# Connector.net
KiCad netlist of a schematic drawn in Altium Designer
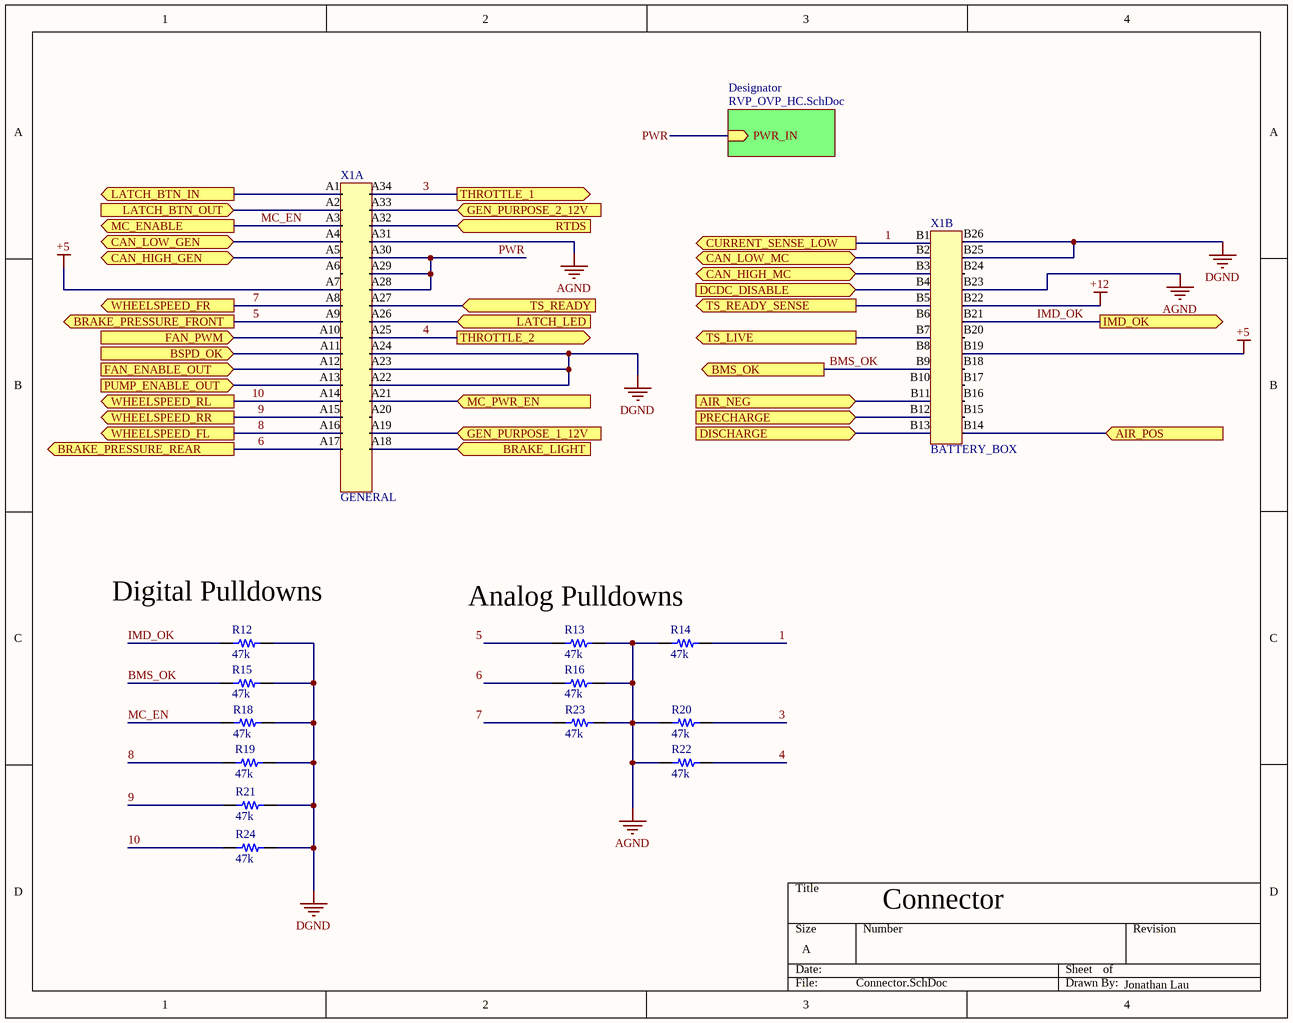
[diagram p0: Connector.SchDoc]

(export (version "E")
  (design (tool "Eeschema 10.0.6"))
  (components
    (comp (ref "R12")
      (value "47k")
      (footprint "RES 0805/2012")
      (fields
        (field (name "TOLERANCE") "1%")
        (field (name "POWER") "1/10W")
        (field (name "Comment") "Resistor 47k 0805 1/10W 1%")
        (field (name "CREATED_BY") "Nick Mah")
      )
      (libsource (lib "Altium-Lib") (part "Resistor"))
    )
    (comp (ref "R13")
      (value "47k")
      (footprint "RES 0805/2012")
      (fields
        (field (name "TOLERANCE") "5%")
        (field (name "POWER") "1/10W")
        (field (name "Comment") "Resistor 47k 0805 1/10W 5%")
        (field (name "CREATED_BY") "Nick Mah")
      )
      (libsource (lib "Altium-Lib") (part "Resistor"))
    )
    (comp (ref "R14")
      (value "47k")
      (footprint "RES 0805/2012")
      (fields
        (field (name "TOLERANCE") "5%")
        (field (name "POWER") "1/10W")
        (field (name "Comment") "Resistor 47k 0805 1/10W 5%")
        (field (name "CREATED_BY") "Nick Mah")
      )
      (libsource (lib "Altium-Lib") (part "Resistor"))
    )
    (comp (ref "R15")
      (value "47k")
      (footprint "RES 0805/2012")
      (fields
        (field (name "TOLERANCE") "1%")
        (field (name "POWER") "1/10W")
        (field (name "Comment") "Resistor 47k 0805 1/10W 1%")
        (field (name "CREATED_BY") "Nick Mah")
      )
      (libsource (lib "Altium-Lib") (part "Resistor"))
    )
    (comp (ref "R16")
      (value "47k")
      (footprint "RES 0805/2012")
      (fields
        (field (name "TOLERANCE") "5%")
        (field (name "POWER") "1/10W")
        (field (name "Comment") "Resistor 47k 0805 1/10W 5%")
        (field (name "CREATED_BY") "Nick Mah")
      )
      (libsource (lib "Altium-Lib") (part "Resistor"))
    )
    (comp (ref "R18")
      (value "47k")
      (footprint "RES 0805/2012")
      (fields
        (field (name "TOLERANCE") "1%")
        (field (name "POWER") "1/10W")
        (field (name "Comment") "Resistor 47k 0805 1/10W 1%")
        (field (name "CREATED_BY") "Nick Mah")
      )
      (libsource (lib "Altium-Lib") (part "Resistor"))
    )
    (comp (ref "R19")
      (value "47k")
      (footprint "RES 0805/2012")
      (fields
        (field (name "TOLERANCE") "5%")
        (field (name "POWER") "1/10W")
        (field (name "Comment") "Resistor 47k 0805 1/10W 5%")
        (field (name "CREATED_BY") "Nick Mah")
      )
      (libsource (lib "Altium-Lib") (part "Resistor"))
    )
    (comp (ref "R20")
      (value "47k")
      (footprint "RES 0805/2012")
      (fields
        (field (name "TOLERANCE") "5%")
        (field (name "POWER") "1/10W")
        (field (name "Comment") "Resistor 47k 0805 1/10W 5%")
        (field (name "CREATED_BY") "Nick Mah")
      )
      (libsource (lib "Altium-Lib") (part "Resistor"))
    )
    (comp (ref "R21")
      (value "47k")
      (footprint "RES 0805/2012")
      (fields
        (field (name "TOLERANCE") "5%")
        (field (name "POWER") "1/10W")
        (field (name "Comment") "Resistor 47k 0805 1/10W 5%")
        (field (name "CREATED_BY") "Nick Mah")
      )
      (libsource (lib "Altium-Lib") (part "Resistor"))
    )
    (comp (ref "R22")
      (value "47k")
      (footprint "RES 0805/2012")
      (fields
        (field (name "TOLERANCE") "5%")
        (field (name "POWER") "1/10W")
        (field (name "Comment") "Resistor 47k 0805 1/10W 5%")
        (field (name "CREATED_BY") "Nick Mah")
      )
      (libsource (lib "Altium-Lib") (part "Resistor"))
    )
    (comp (ref "R23")
      (value "47k")
      (footprint "RES 0805/2012")
      (fields
        (field (name "TOLERANCE") "5%")
        (field (name "POWER") "1/10W")
        (field (name "Comment") "Resistor 47k 0805 1/10W 5%")
        (field (name "CREATED_BY") "Nick Mah")
      )
      (libsource (lib "Altium-Lib") (part "Resistor"))
    )
    (comp (ref "R24")
      (value "47k")
      (footprint "RES 0805/2012")
      (fields
        (field (name "TOLERANCE") "5%")
        (field (name "POWER") "1/10W")
        (field (name "Comment") "Resistor 47k 0805 1/10W 5%")
        (field (name "CREATED_BY") "Nick Mah")
      )
      (libsource (lib "Altium-Lib") (part "Resistor"))
    )
    (comp (ref "X1")
      (value "GENERAL")
      (footprint "SUPERSEAL 60POS 90Deg")
      (description "90 Degree")
      (fields (field (name "MFRPARTNO") "3-6437285-2"))
      (libsource (lib "Altium-Lib") (part "CONN Superseal 60POS"))
    )
  )
  (nets
    (net (code "1") (name "+5") (class "Default")
      (node (ref "X1") (pin "A7") (pintype "bidirectional"))
      (node (ref "X1") (pin "B19") (pintype "bidirectional"))
    )
    (net (code "2") (name "+12") (class "Default") (node (ref "X1") (pin "B22") (pintype "bidirectional")))
    (net (code "3") (name "/1") (class "Default")
      (node (ref "R14") (pin "2") (pinfunction "2_2") (pintype "passive"))
      (node (ref "X1") (pin "B1") (pintype "bidirectional"))
    )
    (net (code "4") (name "/3") (class "Default")
      (node (ref "R20") (pin "2") (pinfunction "2_2") (pintype "passive"))
      (node (ref "X1") (pin "A34") (pintype "bidirectional"))
    )
    (net (code "5") (name "/4") (class "Default")
      (node (ref "R22") (pin "2") (pinfunction "2_2") (pintype "passive"))
      (node (ref "X1") (pin "A25") (pintype "bidirectional"))
    )
    (net (code "6") (name "/5") (class "Default")
      (node (ref "R13") (pin "1") (pinfunction "1_1") (pintype "passive"))
      (node (ref "X1") (pin "A9") (pintype "bidirectional"))
    )
    (net (code "7") (name "/6") (class "Default")
      (node (ref "R16") (pin "1") (pinfunction "1_1") (pintype "passive"))
      (node (ref "X1") (pin "A17") (pintype "bidirectional"))
    )
    (net (code "8") (name "/7") (class "Default")
      (node (ref "R23") (pin "1") (pinfunction "1_1") (pintype "passive"))
      (node (ref "X1") (pin "A8") (pintype "bidirectional"))
    )
    (net (code "9") (name "/8") (class "Default")
      (node (ref "R19") (pin "1") (pinfunction "1_1") (pintype "passive"))
      (node (ref "X1") (pin "A16") (pintype "bidirectional"))
    )
    (net (code "10") (name "/9") (class "Default")
      (node (ref "R21") (pin "1") (pinfunction "1_1") (pintype "passive"))
      (node (ref "X1") (pin "A15") (pintype "bidirectional"))
    )
    (net (code "11") (name "/10") (class "Default")
      (node (ref "R24") (pin "1") (pinfunction "1_1") (pintype "passive"))
      (node (ref "X1") (pin "A14") (pintype "bidirectional"))
    )
    (net (code "12") (name "/AIR_NEG") (class "Default")
      (node (ref "X1") (pin "B11") (pintype "bidirectional"))
    )
    (net (code "13") (name "/AIR_POS") (class "Default")
      (node (ref "X1") (pin "B14") (pintype "bidirectional"))
    )
    (net (code "14") (name "/BMS_OK") (class "Default")
      (node (ref "R15") (pin "1") (pinfunction "1_1") (pintype "passive"))
      (node (ref "X1") (pin "B9") (pintype "bidirectional"))
    )
    (net (code "15") (name "/BRAKE_LIGHT") (class "Default")
      (node (ref "X1") (pin "A18") (pintype "bidirectional"))
    )
    (net (code "16") (name "/BSPD_OK") (class "Default")
      (node (ref "X1") (pin "A11") (pintype "bidirectional"))
    )
    (net (code "17") (name "/CAN_HIGH_GEN") (class "Default")
      (node (ref "X1") (pin "A5") (pintype "bidirectional"))
    )
    (net (code "18") (name "/CAN_HIGH_MC") (class "Default")
      (node (ref "X1") (pin "B3") (pintype "bidirectional"))
    )
    (net (code "19") (name "/CAN_LOW_GEN") (class "Default")
      (node (ref "X1") (pin "A4") (pintype "bidirectional"))
    )
    (net (code "20") (name "/CAN_LOW_MC") (class "Default")
      (node (ref "X1") (pin "B2") (pintype "bidirectional"))
    )
    (net (code "21") (name "/DCDC_DISABLE") (class "Default")
      (node (ref "X1") (pin "B4") (pintype "bidirectional"))
    )
    (net (code "22") (name "/DISCHARGE") (class "Default")
      (node (ref "X1") (pin "B13") (pintype "bidirectional"))
    )
    (net (code "23") (name "/FAN_ENABLE_OUT") (class "Default")
      (node (ref "X1") (pin "A12") (pintype "bidirectional"))
    )
    (net (code "24") (name "/FAN_PWM") (class "Default")
      (node (ref "X1") (pin "A10") (pintype "bidirectional"))
    )
    (net (code "25") (name "/GEN_PURPOSE_1_12V") (class "Default")
      (node (ref "X1") (pin "A19") (pintype "bidirectional"))
    )
    (net (code "26") (name "/GEN_PURPOSE_2_12V") (class "Default")
      (node (ref "X1") (pin "A33") (pintype "bidirectional"))
    )
    (net (code "27") (name "/IMD_OK") (class "Default")
      (node (ref "R12") (pin "1") (pinfunction "1_1") (pintype "passive"))
      (node (ref "X1") (pin "B21") (pintype "bidirectional"))
    )
    (net (code "28") (name "/LATCH_BTN_IN") (class "Default")
      (node (ref "X1") (pin "A1") (pintype "bidirectional"))
    )
    (net (code "29") (name "/LATCH_BTN_OUT") (class "Default")
      (node (ref "X1") (pin "A2") (pintype "bidirectional"))
    )
    (net (code "30") (name "/LATCH_LED") (class "Default")
      (node (ref "X1") (pin "A26") (pintype "bidirectional"))
    )
    (net (code "31") (name "/MC_EN") (class "Default")
      (node (ref "R18") (pin "1") (pinfunction "1_1") (pintype "passive"))
      (node (ref "X1") (pin "A3") (pintype "bidirectional"))
    )
    (net (code "32") (name "/MC_PWR_EN") (class "Default")
      (node (ref "X1") (pin "A21") (pintype "bidirectional"))
    )
    (net (code "33") (name "/PRECHARGE") (class "Default")
      (node (ref "X1") (pin "B12") (pintype "bidirectional"))
    )
    (net (code "34") (name "/PUMP_ENABLE_OUT") (class "Default")
      (node (ref "X1") (pin "A13") (pintype "bidirectional"))
    )
    (net (code "35") (name "/PWR") (class "Default")
      (node (ref "X1") (pin "A28") (pintype "bidirectional"))
      (node (ref "X1") (pin "A29") (pintype "bidirectional"))
      (node (ref "X1") (pin "A30") (pintype "bidirectional"))
    )
    (net (code "36") (name "/RTDS") (class "Default") (node (ref "X1") (pin "A32") (pintype "bidirectional")))
    (net (code "37") (name "/TS_LIVE") (class "Default")
      (node (ref "X1") (pin "B7") (pintype "bidirectional"))
    )
    (net (code "38") (name "/TS_READY") (class "Default")
      (node (ref "X1") (pin "A27") (pintype "bidirectional"))
    )
    (net (code "39") (name "/TS_READY_SENSE") (class "Default")
      (node (ref "X1") (pin "B5") (pintype "bidirectional"))
    )
    (net (code "40") (name "AGND") (class "Default")
      (node (ref "R13") (pin "2") (pinfunction "2_2") (pintype "passive"))
      (node (ref "R14") (pin "1") (pinfunction "1_1") (pintype "passive"))
      (node (ref "R16") (pin "2") (pinfunction "2_2") (pintype "passive"))
      (node (ref "R20") (pin "1") (pinfunction "1_1") (pintype "passive"))
      (node (ref "R22") (pin "1") (pinfunction "1_1") (pintype "passive"))
      (node (ref "R23") (pin "2") (pinfunction "2_2") (pintype "passive"))
      (node (ref "X1") (pin "A31") (pintype "bidirectional"))
      (node (ref "X1") (pin "B23") (pintype "bidirectional"))
    )
    (net (code "41") (name "DGND") (class "Default")
      (node (ref "R12") (pin "2") (pinfunction "2_2") (pintype "passive"))
      (node (ref "R15") (pin "2") (pinfunction "2_2") (pintype "passive"))
      (node (ref "R18") (pin "2") (pinfunction "2_2") (pintype "passive"))
      (node (ref "R19") (pin "2") (pinfunction "2_2") (pintype "passive"))
      (node (ref "R21") (pin "2") (pinfunction "2_2") (pintype "passive"))
      (node (ref "R24") (pin "2") (pinfunction "2_2") (pintype "passive"))
      (node (ref "X1") (pin "A22") (pintype "bidirectional"))
      (node (ref "X1") (pin "A23") (pintype "bidirectional"))
      (node (ref "X1") (pin "A24") (pintype "bidirectional"))
      (node (ref "X1") (pin "B25") (pintype "bidirectional"))
      (node (ref "X1") (pin "B26") (pintype "bidirectional"))
    )
    (net (code "42") (name "unconnected-(X1-PadA6)") (class "Default")
      (node (ref "X1") (pin "A6") (pintype "bidirectional"))
    )
    (net (code "43") (name "unconnected-(X1-PadA20)") (class "Default")
      (node (ref "X1") (pin "A20") (pintype "bidirectional"))
    )
    (net (code "44") (name "unconnected-(X1-PadB6)") (class "Default")
      (node (ref "X1") (pin "B6") (pintype "bidirectional"))
    )
    (net (code "45") (name "unconnected-(X1-PadB8)") (class "Default")
      (node (ref "X1") (pin "B8") (pintype "bidirectional"))
    )
    (net (code "46") (name "unconnected-(X1-PadB10)") (class "Default")
      (node (ref "X1") (pin "B10") (pintype "bidirectional"))
    )
    (net (code "47") (name "unconnected-(X1-PadB15)") (class "Default")
      (node (ref "X1") (pin "B15") (pintype "bidirectional"))
    )
    (net (code "48") (name "unconnected-(X1-PadB16)") (class "Default")
      (node (ref "X1") (pin "B16") (pintype "bidirectional"))
    )
    (net (code "49") (name "unconnected-(X1-PadB17)") (class "Default")
      (node (ref "X1") (pin "B17") (pintype "bidirectional"))
    )
    (net (code "50") (name "unconnected-(X1-PadB18)") (class "Default")
      (node (ref "X1") (pin "B18") (pintype "bidirectional"))
    )
    (net (code "51") (name "unconnected-(X1-PadB20)") (class "Default")
      (node (ref "X1") (pin "B20") (pintype "bidirectional"))
    )
    (net (code "52") (name "unconnected-(X1-PadB24)") (class "Default")
      (node (ref "X1") (pin "B24") (pintype "bidirectional"))
    )
  )
)
